# Power_meter.net
KiCad netlist of a schematic drawn in Altium Designer
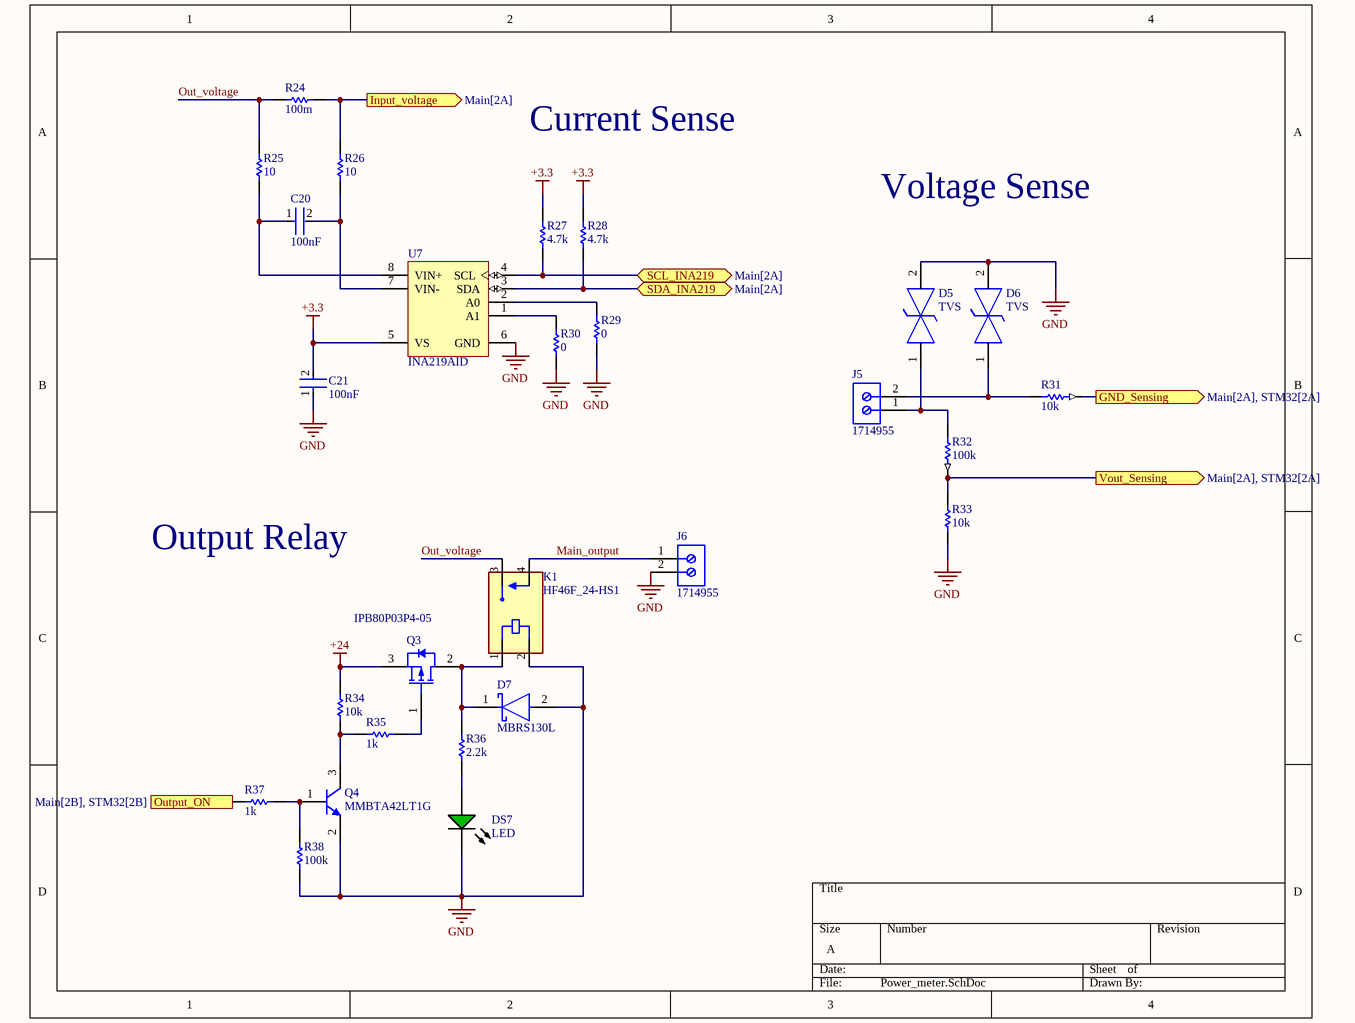
[diagram p0: Power_meter.SchDoc]

(export (version "E")
  (design (tool "Eeschema 10.0.6"))
  (components
    (comp (ref "C20")
      (value "100nF")
      (footprint "FP-0805-L_2_01_0_2-W_1_25-IPC_B")
      (description "General Purpose Ceramic Capacitor, 0805, 100nF, 10%, X7R, 15%, 100V")
      (fields (field (name "VOLTAGE") "100V") (field (name "TOLERANCE") "10%"))
      (libsource (lib "Altium Content Vault") (part "b4654b650e69147ec39a6b967a45e02"))
    )
    (comp (ref "C21")
      (value "100nF")
      (footprint "FP-0805-L_2_01_0_2-W_1_25-IPC_B")
      (description "General Purpose Ceramic Capacitor, 0805, 100nF, 10%, X7R, 15%, 100V")
      (fields (field (name "VOLTAGE") "100V") (field (name "TOLERANCE") "10%"))
      (libsource (lib "Altium Content Vault") (part "b4654b650e69147ec39a6b967a45e02"))
    )
    (comp (ref "D5")
      (value "TVS")
      (footprint "FP-SMB-MFG")
      (description "TVS DIODE 28.2V 59V SMB")
      (fields
        (field (name "OCTOPART") "https://octopart.com/sm6t33ca-stmicroelectronics-55399331")
        (field (name "MANUFACTURER PART NUMBER") "SM6T33CA")
      )
      (libsource (lib "Altium Content Vault") (part "ebc102d6f37e12f28676a717a4d7ff6"))
    )
    (comp (ref "D6")
      (value "TVS")
      (footprint "FP-SMB-MFG")
      (description "TVS DIODE 28.2V 59V SMB")
      (fields
        (field (name "OCTOPART") "https://octopart.com/sm6t33ca-stmicroelectronics-55399331")
        (field (name "MANUFACTURER PART NUMBER") "SM6T33CA")
      )
      (libsource (lib "Altium Content Vault") (part "ebc102d6f37e12f28676a717a4d7ff6"))
    )
    (comp (ref "D7")
      (value "MBRS130L")
      (footprint "FP-403AF-MFG")
      (description "MBRS130L Rectifier Diode, Schottky, 1 Phase, 1 Element, 2A, 30V V(RRM), Silicon, DO-214AA")
      (libsource (lib "Altium Content Vault") (part "1d6ec82d83fb6aee721767c19dac4b9"))
    )
    (comp (ref "DS7")
      (value "LED")
      (footprint "AVAG-HSMX-C170_V")
      (description "Chip LED, Green, 2.2 V, -40 to 85 degC, 2-Pin SMD, Pb-Free, Tape and Reel")
      (fields (field (name "MANUFACTURER") "Avago"))
      (libsource (lib "Altium Content Vault") (part "LED_GREEN_A1K2-2"))
    )
    (comp (ref "J5")
      (value "1714955")
      (footprint "PHOE-1714955_V")
      (description "PC Terminal Block, Pitch 6.35 mm, 1 x 2 Position, Height 21.5 mm, Tail Lenght 5.1 mm, RoHS, Bulk")
      (fields (field (name "MANUFACTURER") "Phoenix Contact"))
      (libsource (lib "Altium Content Vault") (part "CN-1P-F-TB2"))
    )
    (comp (ref "J6")
      (value "1714955")
      (footprint "PHOE-1714955_V")
      (description "PC Terminal Block, Pitch 6.35 mm, 1 x 2 Position, Height 21.5 mm, Tail Lenght 5.1 mm, RoHS, Bulk")
      (fields (field (name "MANUFACTURER") "Phoenix Contact"))
      (libsource (lib "Altium Content Vault") (part "CN-1P-F-TB2"))
    )
    (comp (ref "K1")
      (value "HF46F_24-HS1")
      (footprint "RELAY_HF46F_005-HS1")
      (description "Relay: electromagnetic; SPST-NO; Ucoil: 24VDC; 5A/250VAC; 5A/30VDC")
      (fields (field (name "MF") "Hongfa") (field (name "MP") "HF46F/005-HS1"))
      (libsource (lib "HF46F_005-HS1") (part "HF46F_005-HS1"))
    )
    (comp (ref "Q3")
      (value "IPB80P03P4-05")
      (footprint "INF-PG-TO263-3-2_N")
      (description "OptiMOS-P2 Power-Transistor, -30 V VDS, -80 A ID, PG-TO263-3-2, Reel, Green")
      (fields (field (name "MANUFACTURER") "Infineon"))
      (libsource (lib "Altium Content Vault") (part "INF-MOSFET-P-3"))
    )
    (comp (ref "Q4")
      (value "MMBTA42LT1G")
      (footprint "ONSC-SOT-23-3-318-08_V")
      (description "High Voltage Transistor, NPN Silicon, 3-Pin SOT-23, Pb-Free, Tape and Reel")
      (fields (field (name "MANUFACTURER") "On Semiconductor"))
      (libsource (lib "Altium Content Vault") (part "ONSC-NPN-B1E2C3-3"))
    )
    (comp (ref "R24")
      (value "100m")
      (footprint "RESC3216X70X50NL05T20")
      (description "Shunt resistor")
      (fields (field (name "PART NUMBER") "ERJ8BSFR10V") (field (name "MANUFACTURER") "Panasonic"))
      (libsource (lib "") (part "RES_1"))
    )
    (comp (ref "R25")
      (value "10")
      (footprint "RESC2013X50X30LL20T20")
      (fields (field (name "MANUFACTURER") "Vishay Dale") (field (name "PART NUMBER") "CRCW08050000Z0EA"))
      (libsource (lib "") (part "RES_1"))
    )
    (comp (ref "R26")
      (value "10")
      (footprint "RESC2013X50X30LL20T20")
      (fields (field (name "MANUFACTURER") "Vishay Dale") (field (name "PART NUMBER") "CRCW08050000Z0EA"))
      (libsource (lib "") (part "RES_1"))
    )
    (comp (ref "R27")
      (value "4.7k")
      (footprint "RESC2013X50X30LL20T20")
      (fields (field (name "MANUFACTURER") "Vishay Dale") (field (name "PART NUMBER") "CRCW08050000Z0EA"))
      (libsource (lib "") (part "RES_1"))
    )
    (comp (ref "R28")
      (value "4.7k")
      (footprint "RESC2013X50X30LL20T20")
      (fields (field (name "MANUFACTURER") "Vishay Dale") (field (name "PART NUMBER") "CRCW08050000Z0EA"))
      (libsource (lib "") (part "RES_1"))
    )
    (comp (ref "R29")
      (value "0")
      (footprint "RESC2013X50X30LL20T20")
      (fields (field (name "MANUFACTURER") "Vishay Dale") (field (name "PART NUMBER") "CRCW08050000Z0EA"))
      (libsource (lib "") (part "RES_1"))
    )
    (comp (ref "R30")
      (value "0")
      (footprint "RESC2013X50X30LL20T20")
      (fields (field (name "MANUFACTURER") "Vishay Dale") (field (name "PART NUMBER") "CRCW08050000Z0EA"))
      (libsource (lib "") (part "RES_1"))
    )
    (comp (ref "R31")
      (value "10k")
      (footprint "RESC2013X50X30LL20T20")
      (fields (field (name "MANUFACTURER") "Vishay Dale") (field (name "PART NUMBER") "CRCW08050000Z0EA"))
      (libsource (lib "") (part "RES_2"))
    )
    (comp (ref "R32")
      (value "100k")
      (footprint "RESC2013X50X30LL20T20")
      (fields (field (name "MANUFACTURER") "Vishay Dale") (field (name "PART NUMBER") "CRCW08050000Z0EA"))
      (libsource (lib "Altium Content Vault") (part "RES"))
    )
    (comp (ref "R33")
      (value "10k")
      (footprint "RESC2013X50X30LL20T20")
      (fields (field (name "MANUFACTURER") "Vishay Dale") (field (name "PART NUMBER") "CRCW08050000Z0EA"))
      (libsource (lib "") (part "RES_1"))
    )
    (comp (ref "R34")
      (value "10k")
      (footprint "RESC2013X50X30LL20T20")
      (fields (field (name "MANUFACTURER") "Vishay Dale") (field (name "PART NUMBER") "CRCW08050000Z0EA"))
      (libsource (lib "") (part "RES_1"))
    )
    (comp (ref "R35")
      (value "1k")
      (footprint "RESC2013X50X30LL20T20")
      (fields (field (name "MANUFACTURER") "Vishay Dale") (field (name "PART NUMBER") "CRCW08050000Z0EA"))
      (libsource (lib "") (part "RES_1"))
    )
    (comp (ref "R36")
      (value "2.2k")
      (footprint "RESC2013X50X30LL20T20")
      (fields (field (name "MANUFACTURER") "Vishay Dale") (field (name "PART NUMBER") "CRCW08050000Z0EA"))
      (libsource (lib "") (part "RES_1"))
    )
    (comp (ref "R37")
      (value "1k")
      (footprint "RESC2013X50X30LL20T20")
      (fields (field (name "MANUFACTURER") "Vishay Dale") (field (name "PART NUMBER") "CRCW08050000Z0EA"))
      (libsource (lib "") (part "RES_1"))
    )
    (comp (ref "R38")
      (value "100k")
      (footprint "RESC2013X50X30LL20T20")
      (fields (field (name "MANUFACTURER") "Vishay Dale") (field (name "PART NUMBER") "CRCW08050000Z0EA"))
      (libsource (lib "") (part "RES_1"))
    )
    (comp (ref "U7")
      (value "INA219AID")
      (footprint "D0008A_N")
      (fields (field (name "MANUFACTURER") "Texas Instruments"))
      (libsource (lib "Altium Content Vault") (part "TI-INA219D8"))
    )
  )
  (nets
    (net (code "1") (name "+3.3") (class "Default")
      (node (ref "C21") (pin "2") (pinfunction "2_2") (pintype "passive"))
      (node (ref "R27") (pin "2") (pinfunction "2_2") (pintype "passive"))
      (node (ref "R28") (pin "2") (pinfunction "2_2") (pintype "passive"))
      (node (ref "U7") (pin "5") (pinfunction "VS_5") (pintype "power_in"))
    )
    (net (code "2") (name "+24") (class "Default")
      (node (ref "Q3") (pin "3") (pinfunction "SOURCE_3") (pintype "passive"))
      (node (ref "R34") (pin "2") (pinfunction "2_2") (pintype "passive"))
    )
    (net (code "3") (name "/GND_Sensing") (class "Default")
      (node (ref "R31") (pin "1") (pinfunction "1_1") (pintype "output"))
    )
    (net (code "4") (name "/Input_voltage") (class "Default")
      (node (ref "R24") (pin "2") (pinfunction "2_2") (pintype "passive"))
      (node (ref "R26") (pin "2") (pinfunction "2_2") (pintype "passive"))
    )
    (net (code "5") (name "/Main_output") (class "Default")
      (node (ref "J6") (pin "1") (pinfunction "1_1") (pintype "passive"))
      (node (ref "K1") (pin "4") (pinfunction "NO_4") (pintype "passive"))
    )
    (net (code "6") (name "/Out_voltage") (class "Default")
      (node (ref "K1") (pin "3") (pinfunction "COM_3") (pintype "passive"))
      (node (ref "R24") (pin "1") (pinfunction "1_1") (pintype "passive"))
      (node (ref "R25") (pin "2") (pinfunction "2_2") (pintype "passive"))
    )
    (net (code "7") (name "/Output_ON") (class "Default")
      (node (ref "R37") (pin "1") (pinfunction "1_1") (pintype "passive"))
    )
    (net (code "8") (name "/SCL_INA219") (class "Default")
      (node (ref "R27") (pin "1") (pinfunction "1_1") (pintype "passive"))
      (node (ref "U7") (pin "4") (pinfunction "SCL_4") (pintype "bidirectional"))
    )
    (net (code "9") (name "/SDA_INA219") (class "Default")
      (node (ref "R28") (pin "1") (pinfunction "1_1") (pintype "passive"))
      (node (ref "U7") (pin "3") (pinfunction "SDA_3") (pintype "bidirectional"))
    )
    (net (code "10") (name "/Vout_Sensing") (class "Default")
      (node (ref "R32") (pin "2") (pinfunction "2_2") (pintype "output"))
      (node (ref "R33") (pin "1") (pinfunction "1_1") (pintype "passive"))
    )
    (net (code "11") (name "GND") (class "Default")
      (node (ref "C21") (pin "1") (pinfunction "1_1") (pintype "passive"))
      (node (ref "D5") (pin "2") (pinfunction "2_2") (pintype "passive"))
      (node (ref "D6") (pin "2") (pinfunction "2_2") (pintype "passive"))
      (node (ref "D7") (pin "2") (pinfunction "A_2") (pintype "passive"))
      (node (ref "DS7") (pin "2") (pinfunction "K_2") (pintype "passive"))
      (node (ref "J6") (pin "2") (pinfunction "2_2") (pintype "passive"))
      (node (ref "K1") (pin "2") (pinfunction "COIL2_2") (pintype "passive"))
      (node (ref "Q4") (pin "2") (pinfunction "E_2") (pintype "passive"))
      (node (ref "R29") (pin "1") (pinfunction "1_1") (pintype "passive"))
      (node (ref "R30") (pin "1") (pinfunction "1_1") (pintype "passive"))
      (node (ref "R33") (pin "2") (pinfunction "2_2") (pintype "passive"))
      (node (ref "R38") (pin "1") (pinfunction "1_1") (pintype "passive"))
      (node (ref "U7") (pin "6") (pinfunction "GND_6") (pintype "power_in"))
    )
    (net (code "12") (name "Net-(D5-Pad1)") (class "Default")
      (node (ref "D5") (pin "1") (pinfunction "1_1") (pintype "passive"))
      (node (ref "J5") (pin "1") (pinfunction "1_1") (pintype "passive"))
      (node (ref "R32") (pin "1") (pinfunction "1_1") (pintype "passive"))
    )
    (net (code "13") (name "Net-(D6-Pad1)") (class "Default")
      (node (ref "D6") (pin "1") (pinfunction "1_1") (pintype "passive"))
      (node (ref "J5") (pin "2") (pinfunction "2_2") (pintype "passive"))
      (node (ref "R31") (pin "2") (pinfunction "2_2") (pintype "passive"))
    )
    (net (code "14") (name "Net-(D7-C)") (class "Default")
      (node (ref "D7") (pin "1") (pinfunction "C_1") (pintype "passive"))
      (node (ref "K1") (pin "1") (pinfunction "COIL1_1") (pintype "passive"))
      (node (ref "Q3") (pin "2") (pinfunction "DRAIN_2") (pintype "passive"))
      (node (ref "R36") (pin "2") (pinfunction "2_2") (pintype "passive"))
    )
    (net (code "15") (name "Net-(DS7-A)") (class "Default")
      (node (ref "DS7") (pin "1") (pinfunction "A_1") (pintype "passive"))
      (node (ref "R36") (pin "1") (pinfunction "1_1") (pintype "passive"))
    )
    (net (code "16") (name "Net-(Q3-GATE)") (class "Default")
      (node (ref "Q3") (pin "1") (pinfunction "GATE_1") (pintype "passive"))
      (node (ref "R35") (pin "2") (pinfunction "2_2") (pintype "passive"))
    )
    (net (code "17") (name "Net-(Q4-B)") (class "Default")
      (node (ref "Q4") (pin "1") (pinfunction "B_1") (pintype "passive"))
      (node (ref "R37") (pin "2") (pinfunction "2_2") (pintype "passive"))
      (node (ref "R38") (pin "2") (pinfunction "2_2") (pintype "passive"))
    )
    (net (code "18") (name "Net-(Q4-C)") (class "Default")
      (node (ref "Q4") (pin "3") (pinfunction "C_3") (pintype "passive"))
      (node (ref "R34") (pin "1") (pinfunction "1_1") (pintype "passive"))
      (node (ref "R35") (pin "1") (pinfunction "1_1") (pintype "passive"))
    )
    (net (code "19") (name "Net-(U7-A0)") (class "Default")
      (node (ref "R29") (pin "2") (pinfunction "2_2") (pintype "passive"))
      (node (ref "U7") (pin "2") (pinfunction "A0_2") (pintype "passive"))
    )
    (net (code "20") (name "Net-(U7-A1)") (class "Default")
      (node (ref "R30") (pin "2") (pinfunction "2_2") (pintype "passive"))
      (node (ref "U7") (pin "1") (pinfunction "A1_1") (pintype "passive"))
    )
    (net (code "21") (name "Net-(U7-VIN+)") (class "Default")
      (node (ref "C20") (pin "1") (pinfunction "1_1") (pintype "passive"))
      (node (ref "R25") (pin "1") (pinfunction "1_1") (pintype "passive"))
      (node (ref "U7") (pin "8") (pinfunction "VIN+_8") (pintype "passive"))
    )
    (net (code "22") (name "Net-(U7-VIN-)") (class "Default")
      (node (ref "C20") (pin "2") (pinfunction "2_2") (pintype "passive"))
      (node (ref "R26") (pin "1") (pinfunction "1_1") (pintype "passive"))
      (node (ref "U7") (pin "7") (pinfunction "VIN-_7") (pintype "passive"))
    )
  )
)
